# SCH_BotMark_2026-06-07.net
KiCad netlist of a schematic drawn in EasyEDA
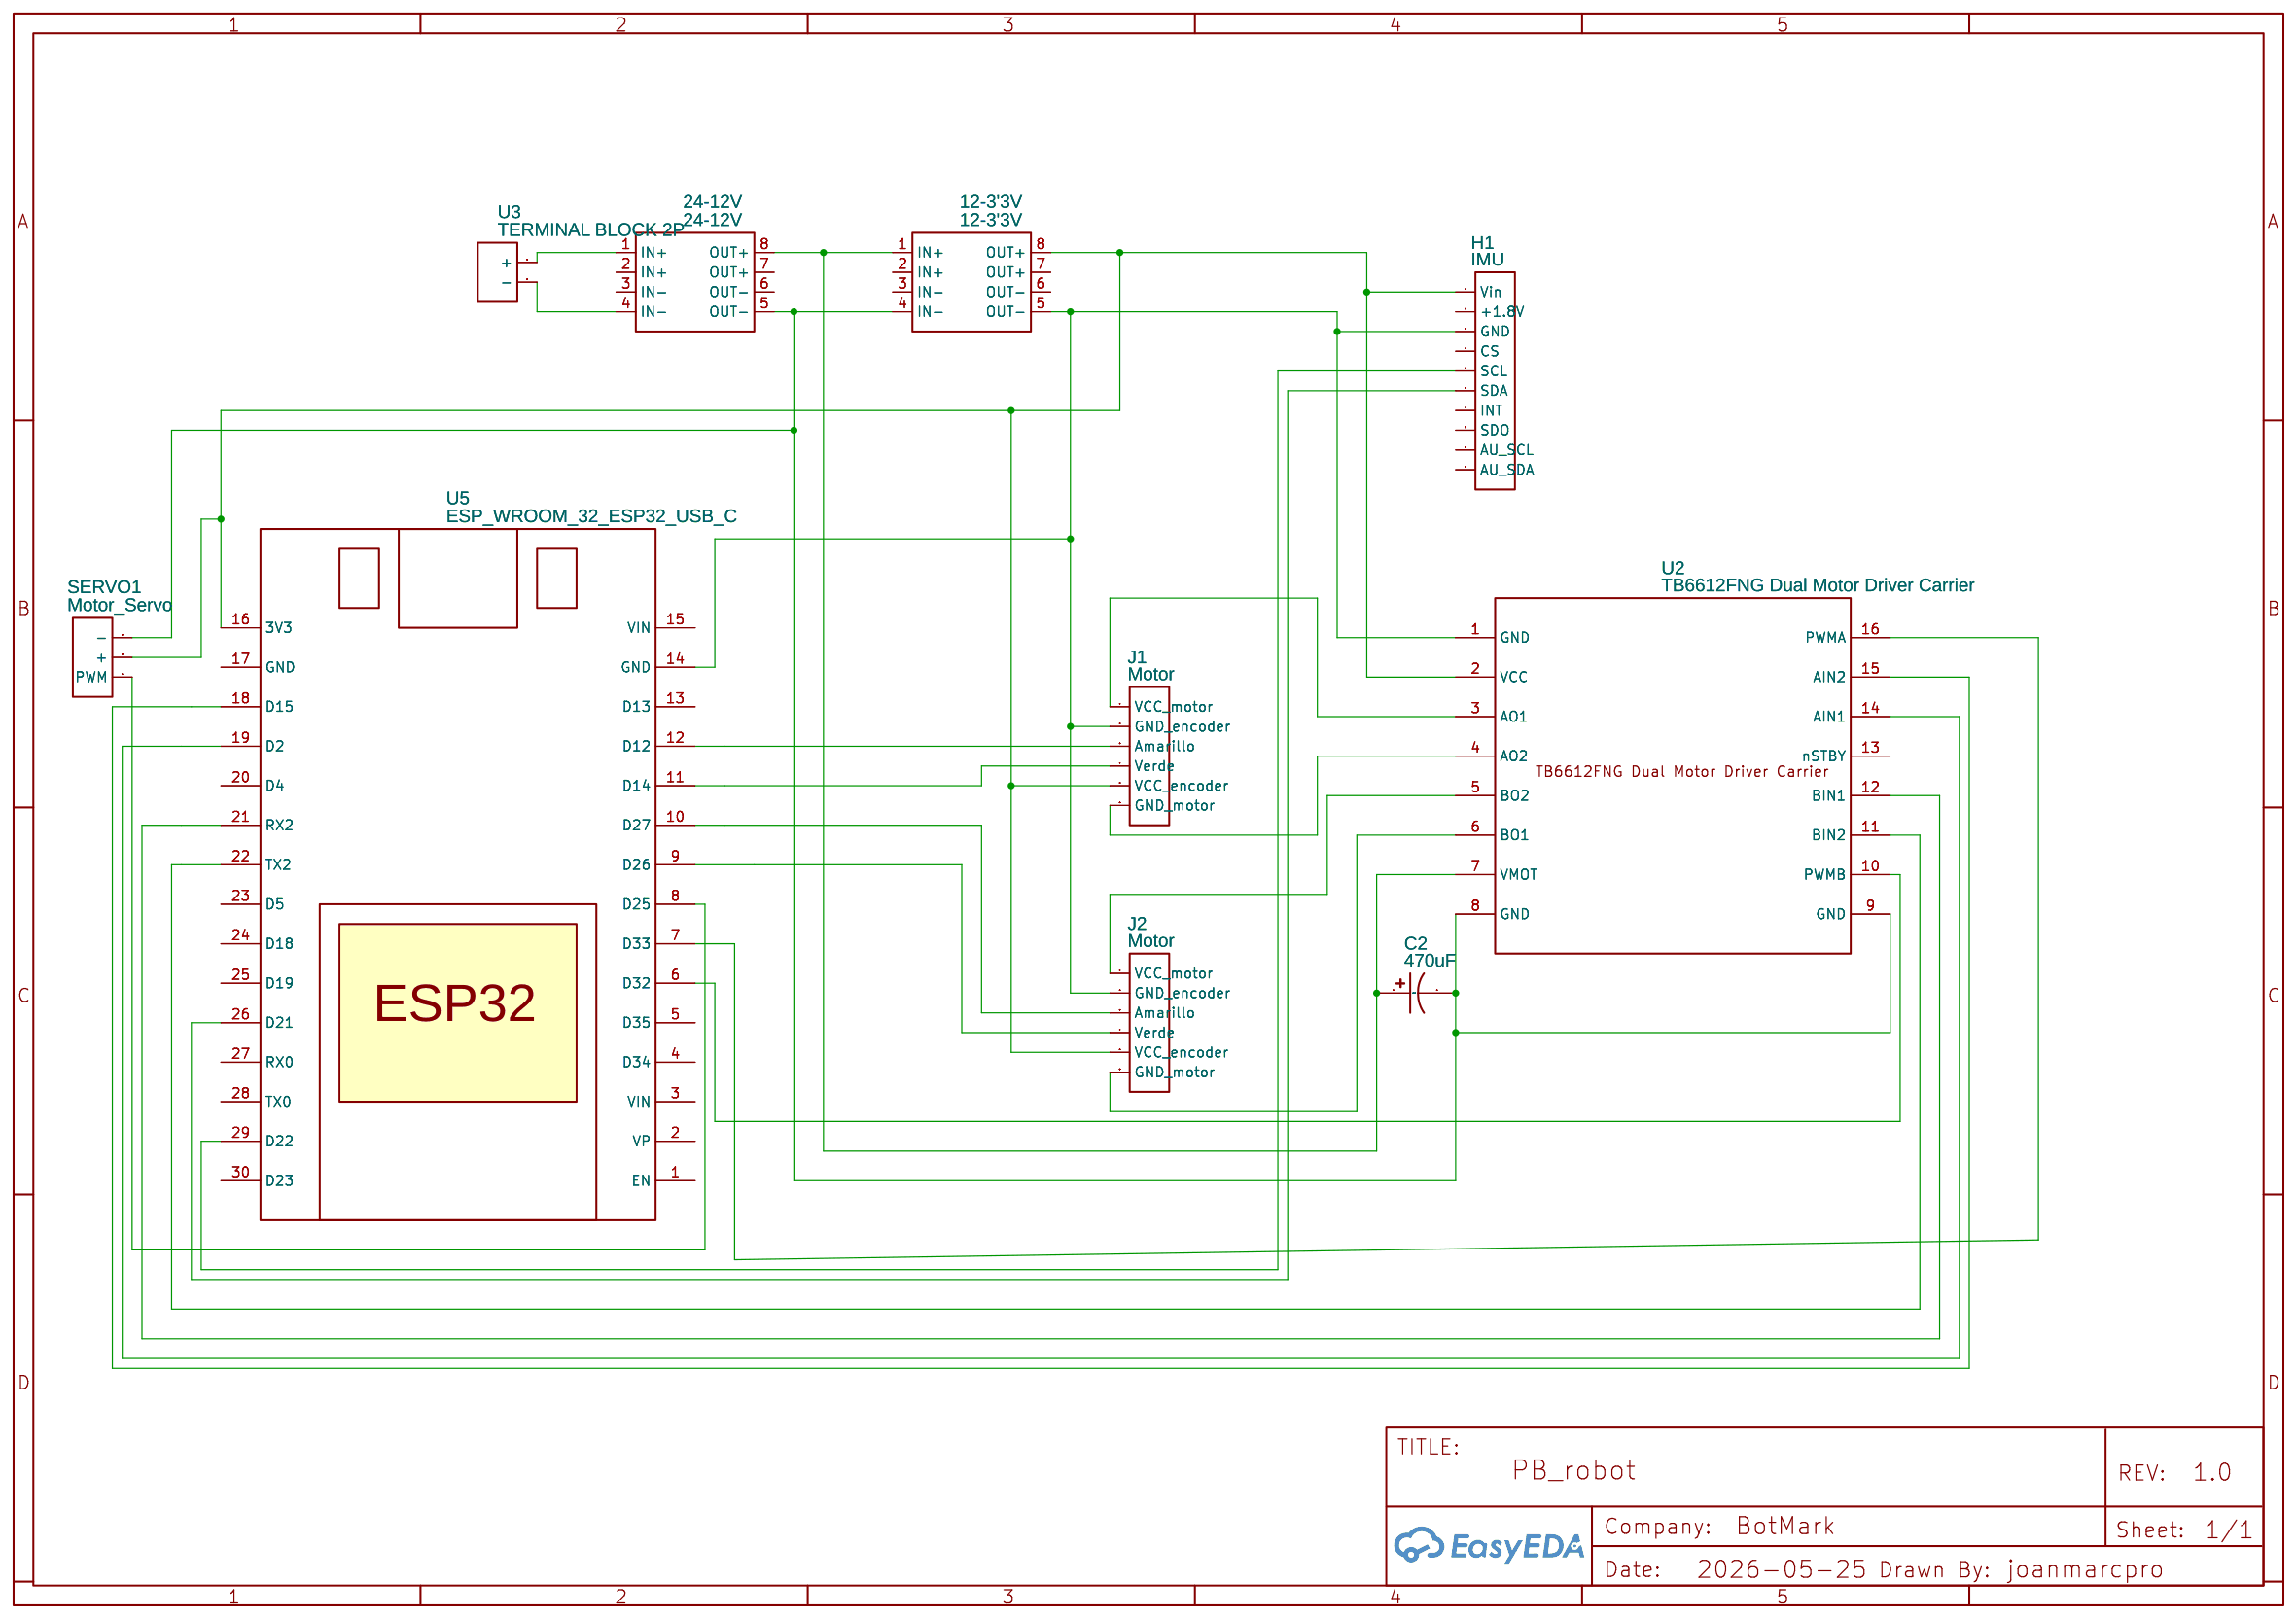
[diagram p0: schematic sheet]

(export (version "E")
  (design (tool "Eeschema 10.0.6"))
  (components
    (comp (ref "12-3'3V")
      (value "12-3'3V")
      (fields (field (name "Manufacturer Part") "MP1584EN_moudle"))
      (libsource (lib "") (part "MP1584EN_MOUDLE_1"))
    )
    (comp (ref "24-12V")
      (value "24-12V")
      (fields (field (name "Manufacturer Part") "MP1584EN_moudle"))
      (libsource (lib "") (part "MP1584EN_MOUDLE"))
    )
    (comp (ref "C2") (value "470uF") (libsource (lib "") (part "CE_TH_D6.3×F2.5_US")))
    (comp (ref "H1") (value "IMU") (libsource (lib "") (part "HDR-F-2.54_1x10")))
    (comp (ref "J1") (value "Motor") (libsource (lib "") (part "HDR-M-2.54_1x6")))
    (comp (ref "J2") (value "Motor") (libsource (lib "") (part "HDR-M-2.54_1x6")))
    (comp (ref "SERVO1") (value "Motor_Servo") (libsource (lib "") (part "HDR-M-2.54_1x3")))
    (comp (ref "U2")
      (value "TB6612FNG Dual Motor Driver Carrier")
      (libsource (lib "") (part "TB6612FNG Dual Motor Driver Carrier"))
    )
    (comp (ref "U3") (value "TERMINAL BLOCK 2P") (libsource (lib "") (part "TERMINAL BLOCK 2P")))
    (comp (ref "U5")
      (value "ESP_WROOM_32_ESP32_USB_C")
      (fields (field (name "Manufacturer Part") "ESP32") (field (name "Manufacturer") "Flutesan"))
      (libsource (lib "") (part "ESP_WROOM_32_ESP32_USB_C"))
    )
  )
  (nets
    (net (code "1") (name "Net-(H1-GND)") (class "Default")
      (node (ref "12-3'3V") (pin "5") (pinfunction "OUT-_5") (pintype "unspecified"))
      (node (ref "H1") (pin "3") (pinfunction "GND_3") (pintype "unspecified"))
      (node (ref "J1") (pin "2") (pinfunction "GND_encoder_2") (pintype "input"))
      (node (ref "J2") (pin "2") (pinfunction "GND_encoder_2") (pintype "input"))
      (node (ref "U2") (pin "1") (pinfunction "GND_1") (pintype "unspecified"))
      (node (ref "U5") (pin "14") (pinfunction "GND_14") (pintype "unspecified"))
    )
    (net (code "2") (name "Net-(H1-SCL)") (class "Default")
      (node (ref "H1") (pin "5") (pinfunction "SCL_5") (pintype "unspecified"))
      (node (ref "U5") (pin "29") (pinfunction "D22_29") (pintype "unspecified"))
    )
    (net (code "3") (name "Net-(H1-SDA)") (class "Default")
      (node (ref "H1") (pin "6") (pinfunction "SDA_6") (pintype "unspecified"))
      (node (ref "U5") (pin "26") (pinfunction "D21_26") (pintype "unspecified"))
    )
    (net (code "4") (name "Net-(H1-Vin)") (class "Default")
      (node (ref "12-3'3V") (pin "8") (pinfunction "OUT+_8") (pintype "unspecified"))
      (node (ref "H1") (pin "1") (pinfunction "Vin_1") (pintype "unspecified"))
      (node (ref "J1") (pin "5") (pinfunction "VCC_encoder_5") (pintype "input"))
      (node (ref "J2") (pin "5") (pinfunction "VCC_encoder_5") (pintype "input"))
      (node (ref "SERVO1") (pin "2") (pinfunction "+_2") (pintype "input"))
      (node (ref "U2") (pin "2") (pinfunction "VCC_2") (pintype "unspecified"))
      (node (ref "U5") (pin "16") (pinfunction "3V3_16") (pintype "unspecified"))
    )
    (net (code "5") (name "Net-(J1-Amarillo)") (class "Default")
      (node (ref "J1") (pin "3") (pinfunction "Amarillo_3") (pintype "input"))
      (node (ref "U5") (pin "12") (pinfunction "D12_12") (pintype "unspecified"))
    )
    (net (code "6") (name "Net-(J1-GND_motor)") (class "Default")
      (node (ref "J1") (pin "6") (pinfunction "GND_motor_6") (pintype "input"))
      (node (ref "U2") (pin "4") (pinfunction "AO2_4") (pintype "unspecified"))
    )
    (net (code "7") (name "Net-(J1-VCC_motor)") (class "Default")
      (node (ref "J1") (pin "1") (pinfunction "VCC_motor_1") (pintype "input"))
      (node (ref "U2") (pin "3") (pinfunction "AO1_3") (pintype "unspecified"))
    )
    (net (code "8") (name "Net-(J1-Verde)") (class "Default")
      (node (ref "J1") (pin "4") (pinfunction "Verde_4") (pintype "input"))
      (node (ref "U5") (pin "11") (pinfunction "D14_11") (pintype "unspecified"))
    )
    (net (code "9") (name "Net-(J2-Amarillo)") (class "Default")
      (node (ref "J2") (pin "3") (pinfunction "Amarillo_3") (pintype "input"))
      (node (ref "U5") (pin "10") (pinfunction "D27_10") (pintype "unspecified"))
    )
    (net (code "10") (name "Net-(J2-GND_motor)") (class "Default")
      (node (ref "J2") (pin "6") (pinfunction "GND_motor_6") (pintype "input"))
      (node (ref "U2") (pin "6") (pinfunction "BO1_6") (pintype "unspecified"))
    )
    (net (code "11") (name "Net-(J2-VCC_motor)") (class "Default")
      (node (ref "J2") (pin "1") (pinfunction "VCC_motor_1") (pintype "input"))
      (node (ref "U2") (pin "5") (pinfunction "BO2_5") (pintype "unspecified"))
    )
    (net (code "12") (name "Net-(J2-Verde)") (class "Default")
      (node (ref "J2") (pin "4") (pinfunction "Verde_4") (pintype "input"))
      (node (ref "U5") (pin "9") (pinfunction "D26_9") (pintype "unspecified"))
    )
    (net (code "13") (name "Net-(SERVO1--)") (class "Default")
      (node (ref "12-3'3V") (pin "4") (pinfunction "IN-_4") (pintype "unspecified"))
      (node (ref "24-12V") (pin "5") (pinfunction "OUT-_5") (pintype "unspecified"))
      (node (ref "C2") (pin "2") (pinfunction "2_2") (pintype "unspecified"))
      (node (ref "SERVO1") (pin "3") (pinfunction "-_3") (pintype "input"))
      (node (ref "U2") (pin "8") (pinfunction "GND_8") (pintype "unspecified"))
      (node (ref "U2") (pin "9") (pinfunction "GND_9") (pintype "unspecified"))
    )
    (net (code "14") (name "Net-(SERVO1-PWM)") (class "Default")
      (node (ref "SERVO1") (pin "1") (pinfunction "PWM_1") (pintype "input"))
      (node (ref "U5") (pin "8") (pinfunction "D25_8") (pintype "unspecified"))
    )
    (net (code "15") (name "Net-(U2-AIN1)") (class "Default")
      (node (ref "U2") (pin "14") (pinfunction "AIN1_14") (pintype "unspecified"))
      (node (ref "U5") (pin "19") (pinfunction "D2_19") (pintype "unspecified"))
    )
    (net (code "16") (name "Net-(U2-AIN2)") (class "Default")
      (node (ref "U2") (pin "15") (pinfunction "AIN2_15") (pintype "unspecified"))
      (node (ref "U5") (pin "18") (pinfunction "D15_18") (pintype "unspecified"))
    )
    (net (code "17") (name "Net-(U2-BIN1)") (class "Default")
      (node (ref "U2") (pin "12") (pinfunction "BIN1_12") (pintype "unspecified"))
      (node (ref "U5") (pin "21") (pinfunction "RX2_21") (pintype "unspecified"))
    )
    (net (code "18") (name "Net-(U2-BIN2)") (class "Default")
      (node (ref "U2") (pin "11") (pinfunction "BIN2_11") (pintype "unspecified"))
      (node (ref "U5") (pin "22") (pinfunction "TX2_22") (pintype "unspecified"))
    )
    (net (code "19") (name "Net-(U2-PWMA)") (class "Default")
      (node (ref "U2") (pin "16") (pinfunction "PWMA_16") (pintype "unspecified"))
      (node (ref "U5") (pin "7") (pinfunction "D33_7") (pintype "unspecified"))
    )
    (net (code "20") (name "Net-(U2-PWMB)") (class "Default")
      (node (ref "U2") (pin "10") (pinfunction "PWMB_10") (pintype "unspecified"))
      (node (ref "U5") (pin "6") (pinfunction "D32_6") (pintype "unspecified"))
    )
    (net (code "21") (name "Net-(U2-VMOT)") (class "Default")
      (node (ref "12-3'3V") (pin "1") (pinfunction "IN+_1") (pintype "unspecified"))
      (node (ref "24-12V") (pin "8") (pinfunction "OUT+_8") (pintype "unspecified"))
      (node (ref "C2") (pin "1") (pinfunction "1_1") (pintype "unspecified"))
      (node (ref "U2") (pin "7") (pinfunction "VMOT_7") (pintype "unspecified"))
    )
    (net (code "22") (name "Net-(U3-+)") (class "Default")
      (node (ref "24-12V") (pin "1") (pinfunction "IN+_1") (pintype "unspecified"))
      (node (ref "U3") (pin "2") (pinfunction "+_2") (pintype "unspecified"))
    )
    (net (code "23") (name "Net-(U3--)") (class "Default")
      (node (ref "24-12V") (pin "4") (pinfunction "IN-_4") (pintype "unspecified"))
      (node (ref "U3") (pin "1") (pinfunction "-_1") (pintype "unspecified"))
    )
    (net (code "24") (name "unconnected-(12-3'3V-IN+-Pad2)") (class "Default")
      (node (ref "12-3'3V") (pin "2") (pinfunction "IN+_2") (pintype "unspecified"))
    )
    (net (code "25") (name "unconnected-(12-3'3V-IN--Pad3)") (class "Default")
      (node (ref "12-3'3V") (pin "3") (pinfunction "IN-_3") (pintype "unspecified"))
    )
    (net (code "26") (name "unconnected-(12-3'3V-OUT+-Pad7)") (class "Default")
      (node (ref "12-3'3V") (pin "7") (pinfunction "OUT+_7") (pintype "unspecified"))
    )
    (net (code "27") (name "unconnected-(12-3'3V-OUT--Pad6)") (class "Default")
      (node (ref "12-3'3V") (pin "6") (pinfunction "OUT-_6") (pintype "unspecified"))
    )
    (net (code "28") (name "unconnected-(24-12V-IN+-Pad2)") (class "Default")
      (node (ref "24-12V") (pin "2") (pinfunction "IN+_2") (pintype "unspecified"))
    )
    (net (code "29") (name "unconnected-(24-12V-IN--Pad3)") (class "Default")
      (node (ref "24-12V") (pin "3") (pinfunction "IN-_3") (pintype "unspecified"))
    )
    (net (code "30") (name "unconnected-(24-12V-OUT+-Pad7)") (class "Default")
      (node (ref "24-12V") (pin "7") (pinfunction "OUT+_7") (pintype "unspecified"))
    )
    (net (code "31") (name "unconnected-(24-12V-OUT--Pad6)") (class "Default")
      (node (ref "24-12V") (pin "6") (pinfunction "OUT-_6") (pintype "unspecified"))
    )
    (net (code "32") (name "unconnected-(H1-+1.8V-Pad2)") (class "Default")
      (node (ref "H1") (pin "2") (pinfunction "+1.8V_2") (pintype "unspecified"))
    )
    (net (code "33") (name "unconnected-(H1-AU_SCL-Pad9)") (class "Default")
      (node (ref "H1") (pin "9") (pinfunction "AU_SCL_9") (pintype "unspecified"))
    )
    (net (code "34") (name "unconnected-(H1-AU_SDA-Pad10)") (class "Default")
      (node (ref "H1") (pin "10") (pinfunction "AU_SDA_10") (pintype "unspecified"))
    )
    (net (code "35") (name "unconnected-(H1-CS-Pad4)") (class "Default")
      (node (ref "H1") (pin "4") (pinfunction "CS_4") (pintype "unspecified"))
    )
    (net (code "36") (name "unconnected-(H1-INT-Pad7)") (class "Default")
      (node (ref "H1") (pin "7") (pinfunction "INT_7") (pintype "unspecified"))
    )
    (net (code "37") (name "unconnected-(H1-SDO-Pad8)") (class "Default")
      (node (ref "H1") (pin "8") (pinfunction "SDO_8") (pintype "unspecified"))
    )
    (net (code "38") (name "unconnected-(U2-nSTBY-Pad13)") (class "Default")
      (node (ref "U2") (pin "13") (pinfunction "nSTBY_13") (pintype "unspecified"))
    )
    (net (code "39") (name "unconnected-(U5-D4-Pad20)") (class "Default")
      (node (ref "U5") (pin "20") (pinfunction "D4_20") (pintype "unspecified"))
    )
    (net (code "40") (name "unconnected-(U5-D5-Pad23)") (class "Default")
      (node (ref "U5") (pin "23") (pinfunction "D5_23") (pintype "unspecified"))
    )
    (net (code "41") (name "unconnected-(U5-D13-Pad13)") (class "Default")
      (node (ref "U5") (pin "13") (pinfunction "D13_13") (pintype "unspecified"))
    )
    (net (code "42") (name "unconnected-(U5-D18-Pad24)") (class "Default")
      (node (ref "U5") (pin "24") (pinfunction "D18_24") (pintype "unspecified"))
    )
    (net (code "43") (name "unconnected-(U5-D19-Pad25)") (class "Default")
      (node (ref "U5") (pin "25") (pinfunction "D19_25") (pintype "unspecified"))
    )
    (net (code "44") (name "unconnected-(U5-D23-Pad30)") (class "Default")
      (node (ref "U5") (pin "30") (pinfunction "D23_30") (pintype "unspecified"))
    )
    (net (code "45") (name "unconnected-(U5-D34-Pad4)") (class "Default")
      (node (ref "U5") (pin "4") (pinfunction "D34_4") (pintype "unspecified"))
    )
    (net (code "46") (name "unconnected-(U5-D35-Pad5)") (class "Default")
      (node (ref "U5") (pin "5") (pinfunction "D35_5") (pintype "unspecified"))
    )
    (net (code "47") (name "unconnected-(U5-EN-Pad1)") (class "Default")
      (node (ref "U5") (pin "1") (pinfunction "EN_1") (pintype "unspecified"))
    )
    (net (code "48") (name "unconnected-(U5-GND-Pad17)") (class "Default")
      (node (ref "U5") (pin "17") (pinfunction "GND_17") (pintype "unspecified"))
    )
    (net (code "49") (name "unconnected-(U5-RX0-Pad27)") (class "Default")
      (node (ref "U5") (pin "27") (pinfunction "RX0_27") (pintype "unspecified"))
    )
    (net (code "50") (name "unconnected-(U5-TX0-Pad28)") (class "Default")
      (node (ref "U5") (pin "28") (pinfunction "TX0_28") (pintype "unspecified"))
    )
    (net (code "51") (name "unconnected-(U5-VIN-Pad3)") (class "Default")
      (node (ref "U5") (pin "3") (pinfunction "VIN_3") (pintype "unspecified"))
    )
    (net (code "52") (name "unconnected-(U5-VIN-Pad15)") (class "Default")
      (node (ref "U5") (pin "15") (pinfunction "VIN_15") (pintype "unspecified"))
    )
    (net (code "53") (name "unconnected-(U5-VP-Pad2)") (class "Default")
      (node (ref "U5") (pin "2") (pinfunction "VP_2") (pintype "unspecified"))
    )
  )
)
